# ATSAM4E16EA_AU_Main_Controller.net
KiCad netlist of a schematic drawn in Altium Designer
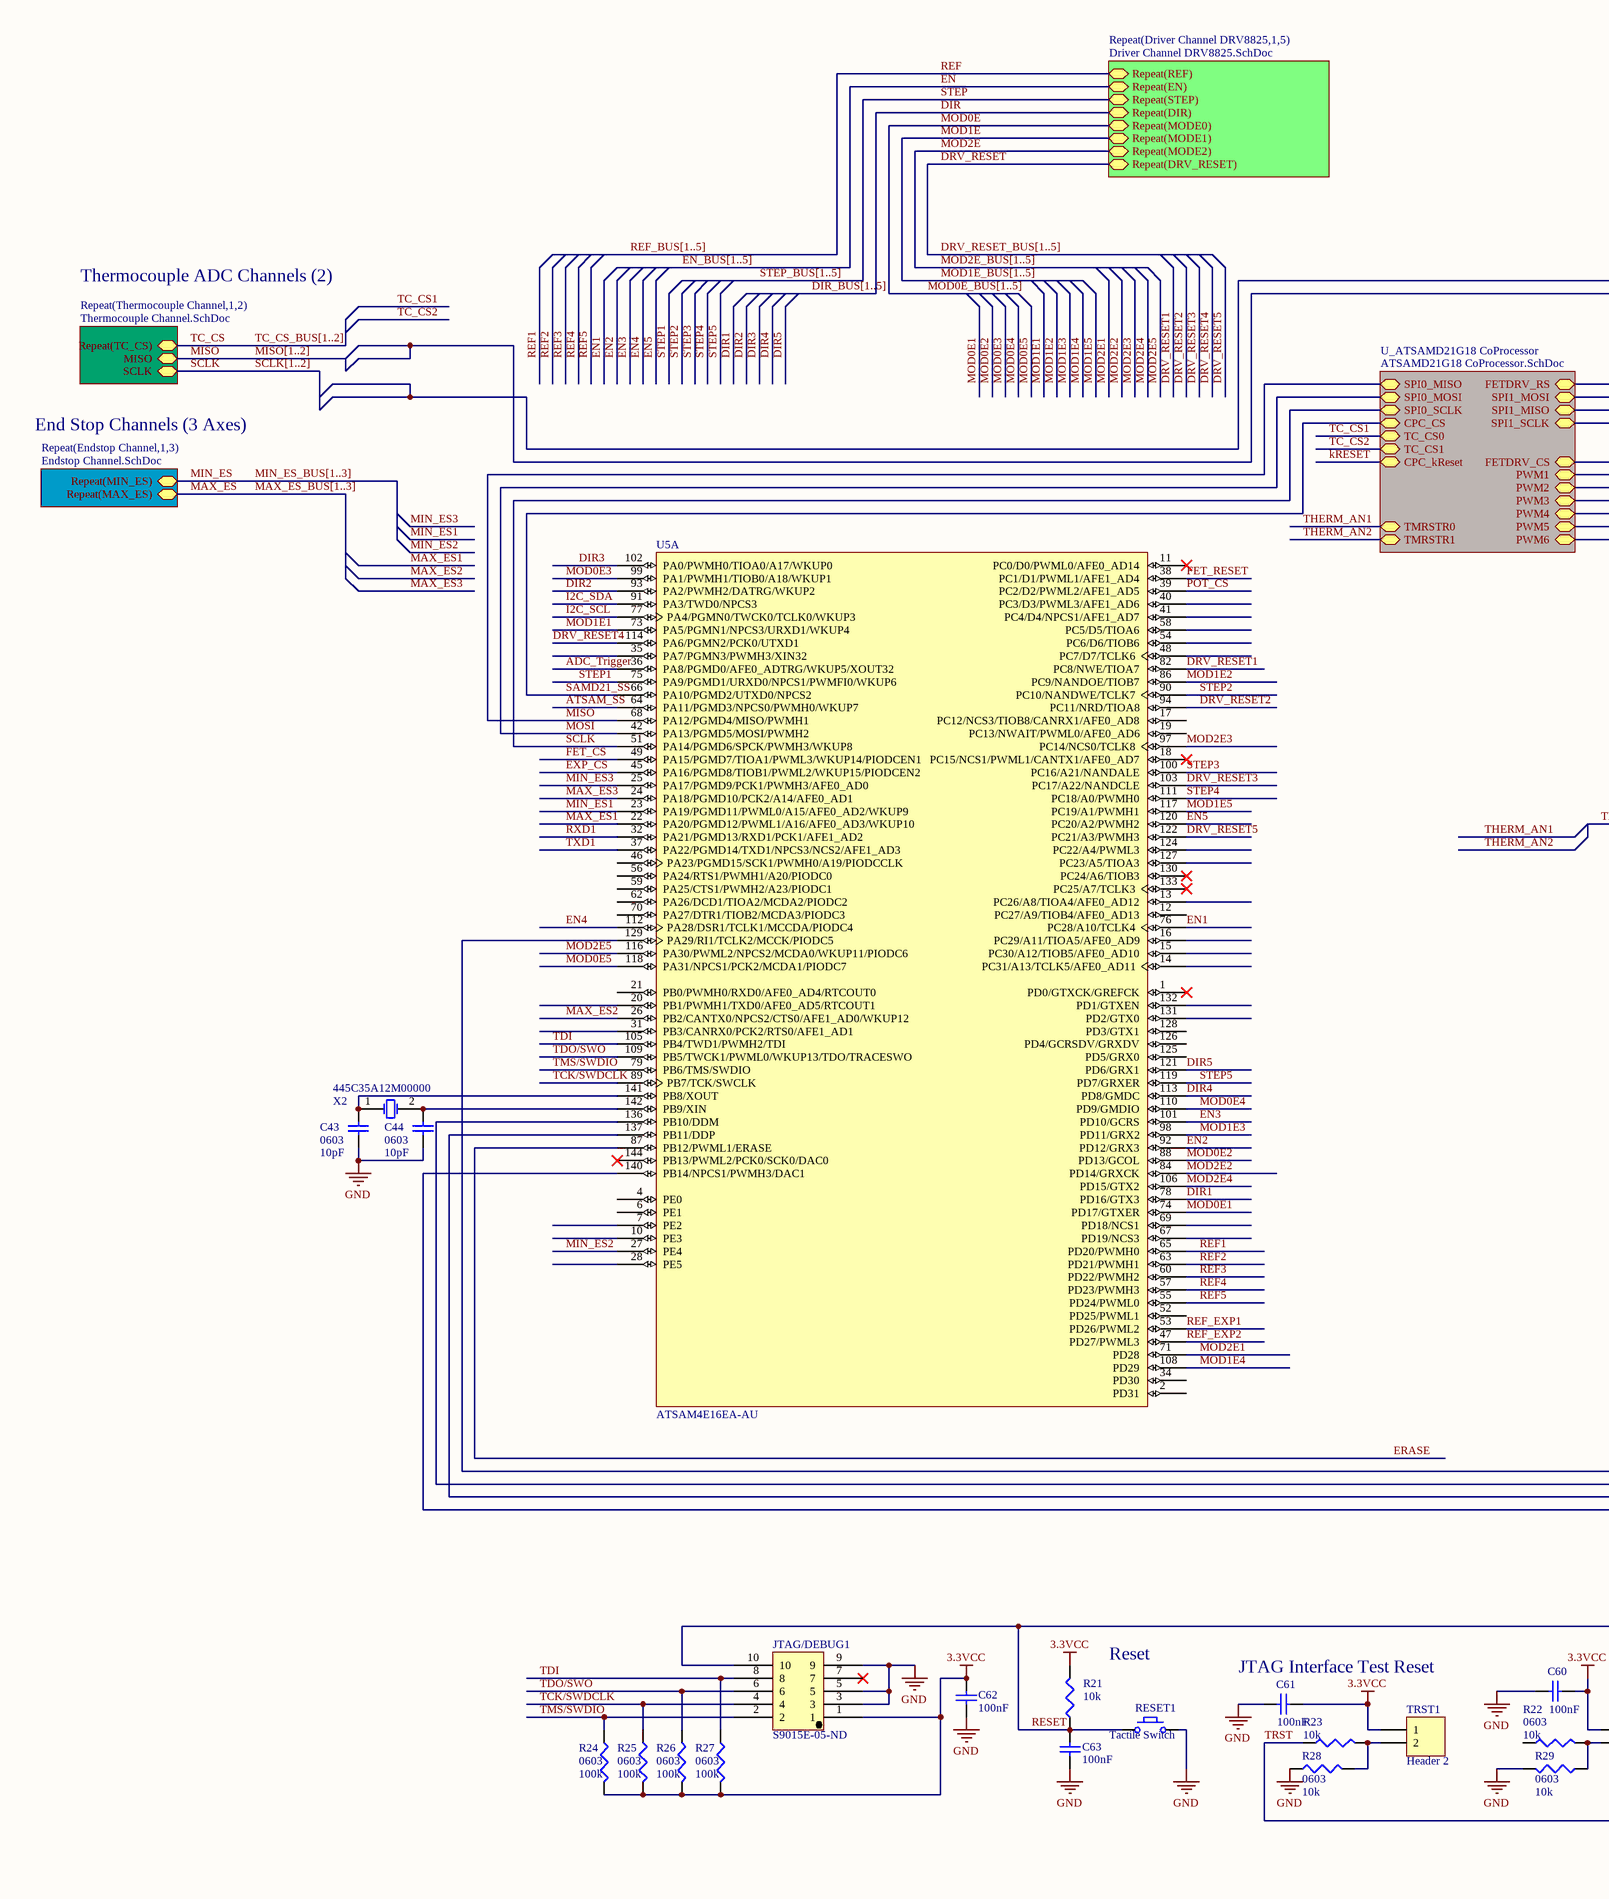
[diagram p0: ATSAM4E16EA_AU Main Controller.SchDoc, left]
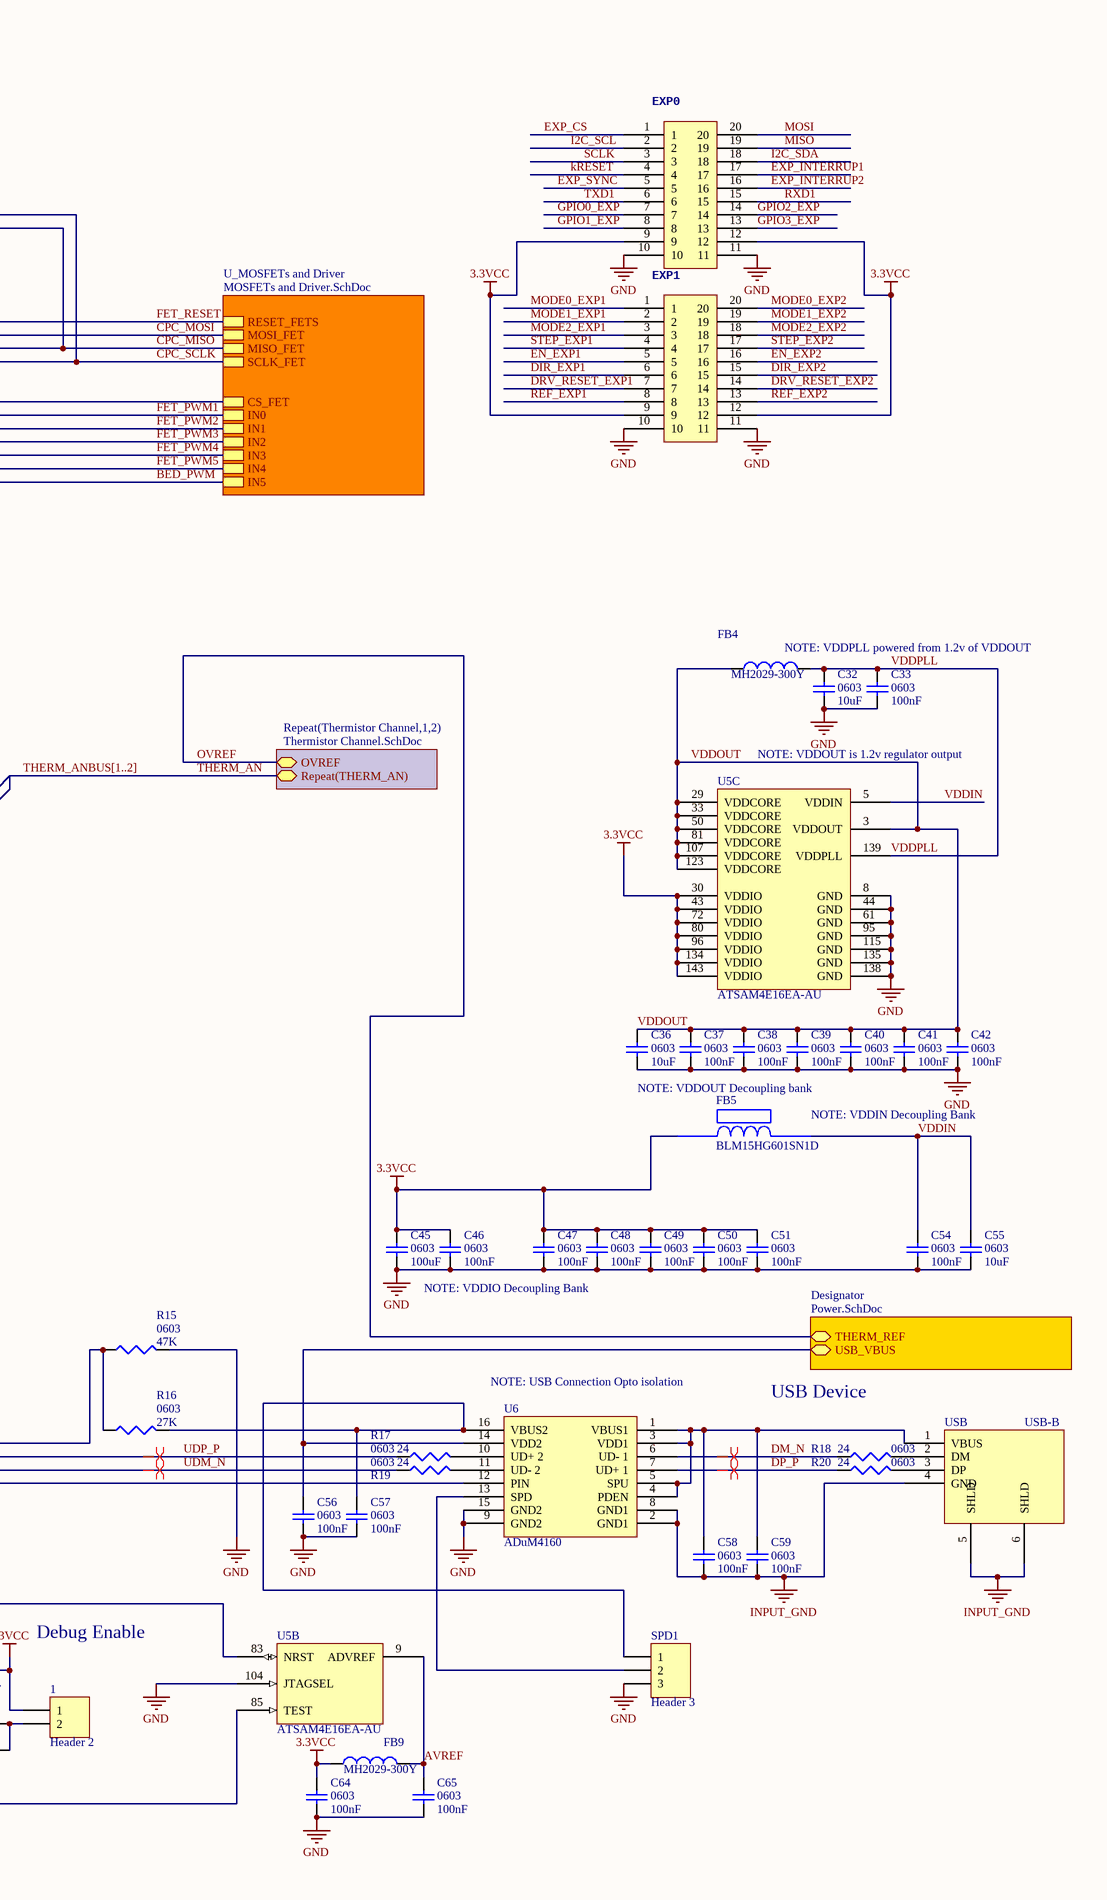
[diagram p1: ATSAM4E16EA_AU Main Controller.SchDoc, right]

(export (version "E")
  (design (tool "Eeschema 10.0.6"))
  (components
    (comp (ref "1")
      (value "Header 2")
      (footprint "HDR1X2")
      (description "Header, 2-Pin")
      (fields (field (name "PUBLISHER") "Altium Limited"))
      (libsource (lib "Miscellaneous Connectors") (part "Header 2"))
    )
    (comp (ref "C32")
      (value "0603")
      (footprint "1608[0603]")
      (description "Capacitor (Semiconductor SIM Model)")
      (fields (field (name "ALTIUM_VALUE") "10uF") (field (name "PUBLISHER") "Altium Limited"))
      (libsource (lib "Miscellaneous Devices") (part "Cap Semi"))
    )
    (comp (ref "C33")
      (value "0603")
      (footprint "1608[0603]")
      (description "Capacitor (Semiconductor SIM Model)")
      (fields (field (name "ALTIUM_VALUE") "100nF") (field (name "PUBLISHER") "Altium Limited"))
      (libsource (lib "Miscellaneous Devices") (part "Cap Semi"))
    )
    (comp (ref "C36")
      (value "0603")
      (footprint "1608[0603]")
      (description "Capacitor (Semiconductor SIM Model)")
      (fields (field (name "ALTIUM_VALUE") "10uF") (field (name "PUBLISHER") "Altium Limited"))
      (libsource (lib "Miscellaneous Devices") (part "Cap Semi"))
    )
    (comp (ref "C37")
      (value "0603")
      (footprint "1608[0603]")
      (description "Capacitor (Semiconductor SIM Model)")
      (fields (field (name "ALTIUM_VALUE") "100nF") (field (name "PUBLISHER") "Altium Limited"))
      (libsource (lib "Miscellaneous Devices") (part "Cap Semi"))
    )
    (comp (ref "C38")
      (value "0603")
      (footprint "1608[0603]")
      (description "Capacitor (Semiconductor SIM Model)")
      (fields (field (name "ALTIUM_VALUE") "100nF") (field (name "PUBLISHER") "Altium Limited"))
      (libsource (lib "Miscellaneous Devices") (part "Cap Semi"))
    )
    (comp (ref "C39")
      (value "0603")
      (footprint "1608[0603]")
      (description "Capacitor (Semiconductor SIM Model)")
      (fields (field (name "ALTIUM_VALUE") "100nF") (field (name "PUBLISHER") "Altium Limited"))
      (libsource (lib "Miscellaneous Devices") (part "Cap Semi"))
    )
    (comp (ref "C40")
      (value "0603")
      (footprint "1608[0603]")
      (description "Capacitor (Semiconductor SIM Model)")
      (fields (field (name "ALTIUM_VALUE") "100nF") (field (name "PUBLISHER") "Altium Limited"))
      (libsource (lib "Miscellaneous Devices") (part "Cap Semi"))
    )
    (comp (ref "C41")
      (value "0603")
      (footprint "1608[0603]")
      (description "Capacitor (Semiconductor SIM Model)")
      (fields (field (name "ALTIUM_VALUE") "100nF") (field (name "PUBLISHER") "Altium Limited"))
      (libsource (lib "Miscellaneous Devices") (part "Cap Semi"))
    )
    (comp (ref "C42")
      (value "0603")
      (footprint "1608[0603]")
      (description "Capacitor (Semiconductor SIM Model)")
      (fields (field (name "ALTIUM_VALUE") "100nF") (field (name "PUBLISHER") "Altium Limited"))
      (libsource (lib "Miscellaneous Devices") (part "Cap Semi"))
    )
    (comp (ref "C43")
      (value "0603")
      (footprint "1608[0603]")
      (description "Capacitor (Semiconductor SIM Model)")
      (fields (field (name "ALTIUM_VALUE") "10pF") (field (name "PUBLISHER") "Altium Limited"))
      (libsource (lib "Miscellaneous Devices") (part "Cap Semi"))
    )
    (comp (ref "C44")
      (value "0603")
      (footprint "1608[0603]")
      (description "Capacitor (Semiconductor SIM Model)")
      (fields (field (name "ALTIUM_VALUE") "10pF") (field (name "PUBLISHER") "Altium Limited"))
      (libsource (lib "Miscellaneous Devices") (part "Cap Semi"))
    )
    (comp (ref "C45")
      (value "0603")
      (footprint "1608[0603]")
      (description "Capacitor (Semiconductor SIM Model)")
      (fields (field (name "ALTIUM_VALUE") "100uF") (field (name "PUBLISHER") "Altium Limited"))
      (libsource (lib "Miscellaneous Devices") (part "Cap Semi"))
    )
    (comp (ref "C46")
      (value "0603")
      (footprint "1608[0603]")
      (description "Capacitor (Semiconductor SIM Model)")
      (fields (field (name "ALTIUM_VALUE") "100nF") (field (name "PUBLISHER") "Altium Limited"))
      (libsource (lib "Miscellaneous Devices") (part "Cap Semi"))
    )
    (comp (ref "C47")
      (value "0603")
      (footprint "1608[0603]")
      (description "Capacitor (Semiconductor SIM Model)")
      (fields (field (name "ALTIUM_VALUE") "100nF") (field (name "PUBLISHER") "Altium Limited"))
      (libsource (lib "Miscellaneous Devices") (part "Cap Semi"))
    )
    (comp (ref "C48")
      (value "0603")
      (footprint "1608[0603]")
      (description "Capacitor (Semiconductor SIM Model)")
      (fields (field (name "ALTIUM_VALUE") "100nF") (field (name "PUBLISHER") "Altium Limited"))
      (libsource (lib "Miscellaneous Devices") (part "Cap Semi"))
    )
    (comp (ref "C49")
      (value "0603")
      (footprint "1608[0603]")
      (description "Capacitor (Semiconductor SIM Model)")
      (fields (field (name "ALTIUM_VALUE") "100nF") (field (name "PUBLISHER") "Altium Limited"))
      (libsource (lib "Miscellaneous Devices") (part "Cap Semi"))
    )
    (comp (ref "C50")
      (value "0603")
      (footprint "1608[0603]")
      (description "Capacitor (Semiconductor SIM Model)")
      (fields (field (name "ALTIUM_VALUE") "100nF") (field (name "PUBLISHER") "Altium Limited"))
      (libsource (lib "Miscellaneous Devices") (part "Cap Semi"))
    )
    (comp (ref "C51")
      (value "0603")
      (footprint "1608[0603]")
      (description "Capacitor (Semiconductor SIM Model)")
      (fields (field (name "ALTIUM_VALUE") "100nF") (field (name "PUBLISHER") "Altium Limited"))
      (libsource (lib "Miscellaneous Devices") (part "Cap Semi"))
    )
    (comp (ref "C54")
      (value "0603")
      (footprint "1608[0603]")
      (description "Capacitor (Semiconductor SIM Model)")
      (fields (field (name "ALTIUM_VALUE") "100nF") (field (name "PUBLISHER") "Altium Limited"))
      (libsource (lib "Miscellaneous Devices") (part "Cap Semi"))
    )
    (comp (ref "C55")
      (value "0603")
      (footprint "1608[0603]")
      (description "Capacitor (Semiconductor SIM Model)")
      (fields (field (name "ALTIUM_VALUE") "10uF") (field (name "PUBLISHER") "Altium Limited"))
      (libsource (lib "Miscellaneous Devices") (part "Cap Semi"))
    )
    (comp (ref "C56")
      (value "0603")
      (footprint "1608[0603]")
      (description "Capacitor (Semiconductor SIM Model)")
      (fields (field (name "ALTIUM_VALUE") "100nF") (field (name "PUBLISHER") "Altium Limited"))
      (libsource (lib "Miscellaneous Devices") (part "Cap Semi"))
    )
    (comp (ref "C57")
      (value "0603")
      (footprint "1608[0603]")
      (description "Capacitor (Semiconductor SIM Model)")
      (fields (field (name "ALTIUM_VALUE") "100nF") (field (name "PUBLISHER") "Altium Limited"))
      (libsource (lib "Miscellaneous Devices") (part "Cap Semi"))
    )
    (comp (ref "C58")
      (value "0603")
      (footprint "1608[0603]")
      (description "Capacitor (Semiconductor SIM Model)")
      (fields (field (name "ALTIUM_VALUE") "100nF") (field (name "PUBLISHER") "Altium Limited"))
      (libsource (lib "Miscellaneous Devices") (part "Cap Semi"))
    )
    (comp (ref "C59")
      (value "0603")
      (footprint "1608[0603]")
      (description "Capacitor (Semiconductor SIM Model)")
      (fields (field (name "ALTIUM_VALUE") "100nF") (field (name "PUBLISHER") "Altium Limited"))
      (libsource (lib "Miscellaneous Devices") (part "Cap Semi"))
    )
    (comp (ref "C60")
      (value "100nF")
      (footprint "1608[0603]")
      (description "Capacitor (Semiconductor SIM Model)")
      (fields (field (name "Comment") "Cap Semi") (field (name "PUBLISHER") "Altium Limited"))
      (libsource (lib "Miscellaneous Devices") (part "Cap Semi"))
    )
    (comp (ref "C61")
      (value "100nF")
      (footprint "1608[0603]")
      (description "Capacitor (Semiconductor SIM Model)")
      (fields (field (name "Comment") "Cap Semi") (field (name "PUBLISHER") "Altium Limited"))
      (libsource (lib "Miscellaneous Devices") (part "Cap Semi"))
    )
    (comp (ref "C62")
      (value "100nF")
      (footprint "1608[0603]")
      (description "Capacitor (Semiconductor SIM Model)")
      (fields (field (name "Comment") "Cap Semi") (field (name "PUBLISHER") "Altium Limited"))
      (libsource (lib "Miscellaneous Devices") (part "Cap Semi"))
    )
    (comp (ref "C63")
      (value "100nF")
      (footprint "1608[0603]")
      (description "Capacitor (Semiconductor SIM Model)")
      (fields (field (name "Comment") "Cap Semi") (field (name "PUBLISHER") "Altium Limited"))
      (libsource (lib "Miscellaneous Devices") (part "Cap Semi"))
    )
    (comp (ref "C64")
      (value "0603")
      (footprint "1608[0603]")
      (description "Capacitor (Semiconductor SIM Model)")
      (fields (field (name "ALTIUM_VALUE") "100nF") (field (name "PUBLISHER") "Altium Limited"))
      (libsource (lib "Miscellaneous Devices") (part "Cap Semi"))
    )
    (comp (ref "C65")
      (value "0603")
      (footprint "1608[0603]")
      (description "Capacitor (Semiconductor SIM Model)")
      (fields (field (name "ALTIUM_VALUE") "100nF") (field (name "PUBLISHER") "Altium Limited"))
      (libsource (lib "Miscellaneous Devices") (part "Cap Semi"))
    )
    (comp (ref "EXP0")
      (value "10X2-0.1X0.05")
      (footprint "10X2-0.05X0.1")
      (fields (field (name "PUBLISHER") "UltiMachine"))
      (libsource (lib "ZMBo Schematic Library") (part "10X2-0.1X0.05"))
    )
    (comp (ref "EXP1")
      (value "10X2-0.1X0.05")
      (footprint "10X2-0.05X0.1")
      (fields (field (name "PUBLISHER") "UltiMachine"))
      (libsource (lib "ZMBo Schematic Library") (part "10X2-0.1X0.05"))
    )
    (comp (ref "FB4")
      (value "MH2029-300Y")
      (footprint "SM 0805 - gap trimmed")
      (description "Inductor")
      (fields (field (name "PUBLISHER") "Altium Limited"))
      (libsource (lib "Miscellaneous Devices") (part "Inductor"))
    )
    (comp (ref "FB5")
      (value "BLM15HG601SN1D")
      (footprint "BLM18PG121SN1D")
      (libsource (lib "AHD Part Library") (part "BLM15HG601SN1D"))
    )
    (comp (ref "FB9")
      (value "MH2029-300Y")
      (footprint "SM 0805 - gap trimmed")
      (description "Inductor")
      (fields (field (name "PUBLISHER") "Altium Limited"))
      (libsource (lib "Miscellaneous Devices") (part "Inductor"))
    )
    (comp (ref "JTAG/DEBUG1")
      (value "S9015E-05-ND")
      (footprint "S9015E-05-ND")
      (libsource (lib "AHD Part Library") (part "S9015E-05-ND"))
    )
    (comp (ref "R15")
      (value "0603")
      (footprint "J1-0603")
      (description "Resistor")
      (fields (field (name "ALTIUM_VALUE") "47K") (field (name "PUBLISHER") "Altium Limited"))
      (libsource (lib "Miscellaneous Devices") (part "Res3"))
    )
    (comp (ref "R16")
      (value "0603")
      (footprint "J1-0603")
      (description "Resistor")
      (fields (field (name "ALTIUM_VALUE") "27K") (field (name "PUBLISHER") "Altium Limited"))
      (libsource (lib "Miscellaneous Devices") (part "Res3"))
    )
    (comp (ref "R17")
      (value "0603")
      (footprint "J1-0603")
      (description "Resistor")
      (fields (field (name "ALTIUM_VALUE") "24") (field (name "PUBLISHER") "Altium Limited"))
      (libsource (lib "Miscellaneous Devices") (part "Res3"))
    )
    (comp (ref "R18")
      (value "0603")
      (footprint "J1-0603")
      (description "Resistor")
      (fields (field (name "ALTIUM_VALUE") "24") (field (name "PUBLISHER") "Altium Limited"))
      (libsource (lib "Miscellaneous Devices") (part "Res3"))
    )
    (comp (ref "R19")
      (value "0603")
      (footprint "J1-0603")
      (description "Resistor")
      (fields (field (name "ALTIUM_VALUE") "24") (field (name "PUBLISHER") "Altium Limited"))
      (libsource (lib "Miscellaneous Devices") (part "Res3"))
    )
    (comp (ref "R20")
      (value "0603")
      (footprint "J1-0603")
      (description "Resistor")
      (fields (field (name "ALTIUM_VALUE") "24") (field (name "PUBLISHER") "Altium Limited"))
      (libsource (lib "Miscellaneous Devices") (part "Res3"))
    )
    (comp (ref "R21")
      (value "10k")
      (footprint "J1-0603")
      (description "Resistor")
      (fields (field (name "Comment") "Res3") (field (name "PUBLISHER") "Altium Limited"))
      (libsource (lib "Miscellaneous Devices") (part "Res3"))
    )
    (comp (ref "R22")
      (value "0603")
      (footprint "J1-0603")
      (description "Resistor")
      (fields (field (name "ALTIUM_VALUE") "10k") (field (name "PUBLISHER") "Altium Limited"))
      (libsource (lib "Miscellaneous Devices") (part "Res3"))
    )
    (comp (ref "R23")
      (value "10k")
      (footprint "J1-0603")
      (description "Resistor")
      (fields (field (name "Comment") "Res3") (field (name "PUBLISHER") "Altium Limited"))
      (libsource (lib "Miscellaneous Devices") (part "Res3"))
    )
    (comp (ref "R24")
      (value "0603")
      (footprint "J1-0603")
      (description "Resistor")
      (fields (field (name "ALTIUM_VALUE") "100k") (field (name "PUBLISHER") "Altium Limited"))
      (libsource (lib "Miscellaneous Devices") (part "Res3"))
    )
    (comp (ref "R25")
      (value "0603")
      (footprint "J1-0603")
      (description "Resistor")
      (fields (field (name "ALTIUM_VALUE") "100k") (field (name "PUBLISHER") "Altium Limited"))
      (libsource (lib "Miscellaneous Devices") (part "Res3"))
    )
    (comp (ref "R26")
      (value "0603")
      (footprint "J1-0603")
      (description "Resistor")
      (fields (field (name "ALTIUM_VALUE") "100k") (field (name "PUBLISHER") "Altium Limited"))
      (libsource (lib "Miscellaneous Devices") (part "Res3"))
    )
    (comp (ref "R27")
      (value "0603")
      (footprint "J1-0603")
      (description "Resistor")
      (fields (field (name "ALTIUM_VALUE") "100k") (field (name "PUBLISHER") "Altium Limited"))
      (libsource (lib "Miscellaneous Devices") (part "Res3"))
    )
    (comp (ref "R28")
      (value "0603")
      (footprint "J1-0603")
      (description "Resistor")
      (fields (field (name "ALTIUM_VALUE") "10k") (field (name "PUBLISHER") "Altium Limited"))
      (libsource (lib "Miscellaneous Devices") (part "Res3"))
    )
    (comp (ref "R29")
      (value "0603")
      (footprint "J1-0603")
      (description "Resistor")
      (fields (field (name "ALTIUM_VALUE") "10k") (field (name "PUBLISHER") "Altium Limited"))
      (libsource (lib "Miscellaneous Devices") (part "Res3"))
    )
    (comp (ref "RESET1")
      (value "Tactile Switch")
      (footprint "TL3301")
      (libsource (lib "Adams Altium Library") (part "Tactile Switch"))
    )
    (comp (ref "SPD1")
      (value "Header 3")
      (footprint "HDR1X3")
      (description "Header, 3-Pin")
      (fields (field (name "PUBLISHER") "Altium Limited"))
      (libsource (lib "Miscellaneous Connectors") (part "Header 3"))
    )
    (comp (ref "TRST1")
      (value "Header 2")
      (footprint "HDR1X2")
      (description "Header, 2-Pin")
      (fields (field (name "PUBLISHER") "Altium Limited"))
      (libsource (lib "Miscellaneous Connectors") (part "Header 2"))
    )
    (comp (ref "U5")
      (value "ATSAM4E16EA-AU")
      (footprint "LQFP144_N")
      (libsource (lib "ZMBo Schematic Library") (part "ATML-ATSAM4EXEA-LQFP-144"))
    )
    (comp (ref "U6")
      (value "ADuM4160")
      (footprint "ADuM4160")
      (description "USB Opto Isolator")
      (libsource (lib "ZMBo Schematic Library") (part "ADuM4160"))
    )
    (comp (ref "USB")
      (value "USB-B")
      (footprint "PN61729")
      (libsource (lib "ZMBo Schematic Library") (part "USB-B"))
    )
    (comp (ref "X2")
      (value "445C35A12M00000")
      (footprint "445C35A12M00000")
      (description "Crystal Oscillator")
      (fields (field (name "PUBLISHER") "Altium Limited"))
      (libsource (lib "Miscellaneous Devices") (part "XTAL"))
    )
  )
  (nets
    (net (code "55") (name "/ADC_Trigger") (class "Default")
      (node (ref "U5") (pin "36") (pinfunction "PA8/PGMD0/AFE0_ADTRG/WKUP5/XOUT32_36") (pintype "bidirectional"))
    )
    (net (code "56") (name "/ATSAM_SS") (class "Default")
      (node (ref "U5") (pin "64") (pinfunction "PA11/PGMD3/NPCS0/PWMH0/WKUP7_64") (pintype "bidirectional"))
    )
    (net (code "57") (name "/AVREF") (class "Default")
      (node (ref "C65") (pin "2") (pinfunction "2_2") (pintype "passive"))
      (node (ref "FB9") (pin "2") (pinfunction "2_2") (pintype "passive"))
      (node (ref "U5") (pin "9") (pinfunction "ADVREF_9") (pintype "passive"))
    )
    (net (code "64") (name "/DIR1") (class "Default")
      (node (ref "U5") (pin "78") (pinfunction "PD16/GTX3_78") (pintype "bidirectional"))
    )
    (net (code "65") (name "/DIR2") (class "Default")
      (node (ref "U5") (pin "93") (pinfunction "PA2/PWMH2/DATRG/WKUP2_93") (pintype "bidirectional"))
    )
    (net (code "66") (name "/DIR3") (class "Default")
      (node (ref "U5") (pin "102") (pinfunction "PA0/PWMH0/TIOA0/A17/WKUP0_102") (pintype "bidirectional"))
    )
    (net (code "67") (name "/DIR4") (class "Default")
      (node (ref "U5") (pin "113") (pinfunction "PD8/GMDC_113") (pintype "bidirectional"))
    )
    (net (code "68") (name "/DIR5") (class "Default")
      (node (ref "U5") (pin "121") (pinfunction "PD6/GRX1_121") (pintype "bidirectional"))
    )
    (net (code "70") (name "/DIR_EXP1") (class "Default")
      (node (ref "EXP1") (pin "6") (pinfunction "6_6") (pintype "passive"))
    )
    (net (code "71") (name "/DIR_EXP2") (class "Default")
      (node (ref "EXP1") (pin "15") (pinfunction "15_15") (pintype "passive"))
    )
    (net (code "72") (name "/DM_N") (class "Default")
      (node (ref "R18") (pin "1") (pinfunction "1_1") (pintype "passive"))
      (node (ref "U6") (pin "6") (pinfunction "UD-_1_6") (pintype "passive"))
    )
    (net (code "73") (name "/DP_P") (class "Default")
      (node (ref "R20") (pin "1") (pinfunction "1_1") (pintype "passive"))
      (node (ref "U6") (pin "7") (pinfunction "UD+_1_7") (pintype "passive"))
    )
    (net (code "75") (name "/DRV_RESET1") (class "Default")
      (node (ref "U5") (pin "82") (pinfunction "PC8/NWE/TIOA7_82") (pintype "bidirectional"))
    )
    (net (code "76") (name "/DRV_RESET2") (class "Default")
      (node (ref "U5") (pin "94") (pinfunction "PC11/NRD/TIOA8_94") (pintype "bidirectional"))
    )
    (net (code "77") (name "/DRV_RESET3") (class "Default")
      (node (ref "U5") (pin "103") (pinfunction "PC17/A22/NANDCLE_103") (pintype "bidirectional"))
    )
    (net (code "78") (name "/DRV_RESET4") (class "Default")
      (node (ref "U5") (pin "114") (pinfunction "PA6/PGMN2/PCK0/UTXD1_114") (pintype "bidirectional"))
    )
    (net (code "79") (name "/DRV_RESET5") (class "Default")
      (node (ref "U5") (pin "122") (pinfunction "PC21/A3/PWMH3_122") (pintype "bidirectional"))
    )
    (net (code "81") (name "/DRV_RESET_EXP1") (class "Default")
      (node (ref "EXP1") (pin "7") (pinfunction "7_7") (pintype "passive"))
    )
    (net (code "82") (name "/DRV_RESET_EXP2") (class "Default")
      (node (ref "EXP1") (pin "14") (pinfunction "14_14") (pintype "passive"))
    )
    (net (code "84") (name "/EN1") (class "Default")
      (node (ref "U5") (pin "76") (pinfunction "PC28/A10/TCLK4_76") (pintype "bidirectional"))
    )
    (net (code "85") (name "/EN2") (class "Default")
      (node (ref "U5") (pin "92") (pinfunction "PD12/GRX3_92") (pintype "bidirectional"))
    )
    (net (code "86") (name "/EN3") (class "Default")
      (node (ref "U5") (pin "101") (pinfunction "PD10/GCRS_101") (pintype "bidirectional"))
    )
    (net (code "87") (name "/EN4") (class "Default")
      (node (ref "U5") (pin "112") (pinfunction "PA28/DSR1/TCLK1/MCCDA/PIODC4_112") (pintype "bidirectional"))
    )
    (net (code "88") (name "/EN5") (class "Default")
      (node (ref "U5") (pin "120") (pinfunction "PC20/A2/PWMH2_120") (pintype "bidirectional"))
    )
    (net (code "90") (name "/EN_EXP1") (class "Default")
      (node (ref "EXP1") (pin "5") (pinfunction "5_5") (pintype "passive"))
    )
    (net (code "91") (name "/EN_EXP2") (class "Default")
      (node (ref "EXP1") (pin "16") (pinfunction "16_16") (pintype "passive"))
    )
    (net (code "92") (name "/ERASE") (class "Default")
      (node (ref "U5") (pin "87") (pinfunction "PB12/PWML1/ERASE_87") (pintype "bidirectional"))
    )
    (net (code "93") (name "/EXP_CS") (class "Default")
      (node (ref "EXP0") (pin "1") (pinfunction "1_1") (pintype "passive"))
      (node (ref "U5") (pin "45") (pinfunction "PA16/PGMD8/TIOB1/PWML2/WKUP15/PIODCEN2_45") (pintype "bidirectional"))
    )
    (net (code "94") (name "/EXP_INTERRUP1") (class "Default")
      (node (ref "EXP0") (pin "17") (pinfunction "17_17") (pintype "passive"))
    )
    (net (code "95") (name "/EXP_INTERRUP2") (class "Default")
      (node (ref "EXP0") (pin "16") (pinfunction "16_16") (pintype "passive"))
    )
    (net (code "96") (name "/EXP_SYNC") (class "Default")
      (node (ref "EXP0") (pin "5") (pinfunction "5_5") (pintype "passive"))
    )
    (net (code "97") (name "/FET_CS") (class "Default")
      (node (ref "U5") (pin "49") (pinfunction "PA15/PGMD7/TIOA1/PWML3/WKUP14/PIODCEN1_49") (pintype "bidirectional"))
    )
    (net (code "103") (name "/FET_RESET") (class "Default")
      (node (ref "U5") (pin "38") (pinfunction "PC1/D1/PWML1/AFE1_AD4_38") (pintype "bidirectional"))
    )
    (net (code "104") (name "/GPIO0_EXP") (class "Default")
      (node (ref "EXP0") (pin "7") (pinfunction "7_7") (pintype "passive"))
    )
    (net (code "105") (name "/GPIO1_EXP") (class "Default")
      (node (ref "EXP0") (pin "8") (pinfunction "8_8") (pintype "passive"))
    )
    (net (code "106") (name "/GPIO2_EXP") (class "Default")
      (node (ref "EXP0") (pin "14") (pinfunction "14_14") (pintype "passive"))
    )
    (net (code "107") (name "/GPIO3_EXP") (class "Default")
      (node (ref "EXP0") (pin "13") (pinfunction "13_13") (pintype "passive"))
    )
    (net (code "108") (name "/I2C_SCL") (class "Default")
      (node (ref "EXP0") (pin "2") (pinfunction "2_2") (pintype "passive"))
      (node (ref "U5") (pin "77") (pinfunction "PA4/PGMN0/TWCK0/TCLK0/WKUP3_77") (pintype "bidirectional"))
    )
    (net (code "109") (name "/I2C_SDA") (class "Default")
      (node (ref "EXP0") (pin "18") (pinfunction "18_18") (pintype "passive"))
      (node (ref "U5") (pin "91") (pinfunction "PA3/TWD0/NPCS3_91") (pintype "bidirectional"))
    )
    (net (code "111") (name "/MAX_ES1") (class "Default")
      (node (ref "U5") (pin "22") (pinfunction "PA20/PGMD12/PWML1/A16/AFE0_AD3/WKUP10_22") (pintype "bidirectional"))
    )
    (net (code "112") (name "/MAX_ES2") (class "Default")
      (node (ref "U5") (pin "26") (pinfunction "PB2/CANTX0/NPCS2/CTS0/AFE1_AD0/WKUP12_26") (pintype "bidirectional"))
    )
    (net (code "113") (name "/MAX_ES3") (class "Default")
      (node (ref "U5") (pin "24") (pinfunction "PA18/PGMD10/PCK2/A14/AFE0_AD1_24") (pintype "bidirectional"))
    )
    (net (code "116") (name "/MIN_ES1") (class "Default")
      (node (ref "U5") (pin "23") (pinfunction "PA19/PGMD11/PWML0/A15/AFE0_AD2/WKUP9_23") (pintype "bidirectional"))
    )
    (net (code "117") (name "/MIN_ES2") (class "Default")
      (node (ref "U5") (pin "27") (pinfunction "PE4_27") (pintype "bidirectional"))
    )
    (net (code "118") (name "/MIN_ES3") (class "Default")
      (node (ref "U5") (pin "25") (pinfunction "PA17/PGMD9/PCK1/PWMH3/AFE0_AD0_25") (pintype "bidirectional"))
    )
    (net (code "120") (name "/MISO") (class "Default")
      (node (ref "EXP0") (pin "19") (pinfunction "19_19") (pintype "passive"))
      (node (ref "U5") (pin "68") (pinfunction "PA12/PGMD4/MISO/PWMH1_68") (pintype "bidirectional"))
    )
    (net (code "123") (name "/MOD0E1") (class "Default")
      (node (ref "U5") (pin "74") (pinfunction "PD17/GTXER_74") (pintype "bidirectional"))
    )
    (net (code "124") (name "/MOD0E2") (class "Default")
      (node (ref "U5") (pin "88") (pinfunction "PD13/GCOL_88") (pintype "bidirectional"))
    )
    (net (code "125") (name "/MOD0E3") (class "Default")
      (node (ref "U5") (pin "99") (pinfunction "PA1/PWMH1/TIOB0/A18/WKUP1_99") (pintype "bidirectional"))
    )
    (net (code "126") (name "/MOD0E4") (class "Default")
      (node (ref "U5") (pin "110") (pinfunction "PD9/GMDIO_110") (pintype "bidirectional"))
    )
    (net (code "127") (name "/MOD0E5") (class "Default")
      (node (ref "U5") (pin "118") (pinfunction "PA31/NPCS1/PCK2/MCDA1/PIODC7_118") (pintype "bidirectional"))
    )
    (net (code "130") (name "/MOD1E1") (class "Default")
      (node (ref "U5") (pin "73") (pinfunction "PA5/PGMN1/NPCS3/URXD1/WKUP4_73") (pintype "bidirectional"))
    )
    (net (code "131") (name "/MOD1E2") (class "Default")
      (node (ref "U5") (pin "86") (pinfunction "PC9/NANDOE/TIOB7_86") (pintype "bidirectional"))
    )
    (net (code "132") (name "/MOD1E3") (class "Default")
      (node (ref "U5") (pin "98") (pinfunction "PD11/GRX2_98") (pintype "bidirectional"))
    )
    (net (code "133") (name "/MOD1E4") (class "Default")
      (node (ref "U5") (pin "108") (pinfunction "PD29_108") (pintype "bidirectional"))
    )
    (net (code "134") (name "/MOD1E5") (class "Default")
      (node (ref "U5") (pin "117") (pinfunction "PC19/A1/PWMH1_117") (pintype "bidirectional"))
    )
    (net (code "137") (name "/MOD2E1") (class "Default")
      (node (ref "U5") (pin "71") (pinfunction "PD28_71") (pintype "bidirectional"))
    )
    (net (code "138") (name "/MOD2E2") (class "Default")
      (node (ref "U5") (pin "84") (pinfunction "PD14/GRXCK_84") (pintype "bidirectional"))
    )
    (net (code "139") (name "/MOD2E3") (class "Default")
      (node (ref "U5") (pin "97") (pinfunction "PC14/NCS0/TCLK8_97") (pintype "bidirectional"))
    )
    (net (code "140") (name "/MOD2E4") (class "Default")
      (node (ref "U5") (pin "106") (pinfunction "PD15/GTX2_106") (pintype "bidirectional"))
    )
    (net (code "141") (name "/MOD2E5") (class "Default")
      (node (ref "U5") (pin "116") (pinfunction "PA30/PWML2/NPCS2/MCDA0/WKUP11/PIODC6_116") (pintype "bidirectional"))
    )
    (net (code "143") (name "/MODE0_EXP1") (class "Default")
      (node (ref "EXP1") (pin "1") (pinfunction "1_1") (pintype "passive"))
    )
    (net (code "144") (name "/MODE0_EXP2") (class "Default")
      (node (ref "EXP1") (pin "20") (pinfunction "20_20") (pintype "passive"))
    )
    (net (code "145") (name "/MODE1_EXP1") (class "Default")
      (node (ref "EXP1") (pin "2") (pinfunction "2_2") (pintype "passive"))
    )
    (net (code "146") (name "/MODE1_EXP2") (class "Default")
      (node (ref "EXP1") (pin "19") (pinfunction "19_19") (pintype "passive"))
    )
    (net (code "147") (name "/MODE2_EXP1") (class "Default")
      (node (ref "EXP1") (pin "3") (pinfunction "3_3") (pintype "passive"))
    )
    (net (code "148") (name "/MODE2_EXP2") (class "Default")
      (node (ref "EXP1") (pin "18") (pinfunction "18_18") (pintype "passive"))
    )
    (net (code "149") (name "/MOSI") (class "Default")
      (node (ref "EXP0") (pin "20") (pinfunction "20_20") (pintype "passive"))
      (node (ref "U5") (pin "42") (pinfunction "PA13/PGMD5/MOSI/PWMH2_42") (pintype "bidirectional"))
    )
    (net (code "151") (name "/POT_CS") (class "Default")
      (node (ref "U5") (pin "39") (pinfunction "PC2/D2/PWML2/AFE1_AD5_39") (pintype "bidirectional"))
    )
    (net (code "153") (name "/REF1") (class "Default")
      (node (ref "U5") (pin "65") (pinfunction "PD20/PWMH0_65") (pintype "bidirectional"))
    )
    (net (code "154") (name "/REF2") (class "Default")
      (node (ref "U5") (pin "63") (pinfunction "PD21/PWMH1_63") (pintype "bidirectional"))
    )
    (net (code "155") (name "/REF3") (class "Default")
      (node (ref "U5") (pin "60") (pinfunction "PD22/PWMH2_60") (pintype "bidirectional"))
    )
    (net (code "156") (name "/REF4") (class "Default")
      (node (ref "U5") (pin "57") (pinfunction "PD23/PWMH3_57") (pintype "bidirectional"))
    )
    (net (code "157") (name "/REF5") (class "Default")
      (node (ref "U5") (pin "55") (pinfunction "PD24/PWML0_55") (pintype "bidirectional"))
    )
    (net (code "159") (name "/REF_EXP1") (class "Default")
      (node (ref "EXP1") (pin "8") (pinfunction "8_8") (pintype "passive"))
      (node (ref "U5") (pin "53") (pinfunction "PD26/PWML2_53") (pintype "bidirectional"))
    )
    (net (code "160") (name "/REF_EXP2") (class "Default")
      (node (ref "EXP1") (pin "13") (pinfunction "13_13") (pintype "passive"))
      (node (ref "U5") (pin "47") (pinfunction "PD27/PWML3_47") (pintype "bidirectional"))
    )
    (net (code "161") (name "/RESET") (class "Default")
      (node (ref "C63") (pin "2") (pinfunction "2_2") (pintype "passive"))
      (node (ref "JTAG/DEBUG1") (pin "10") (pinfunction "10_10") (pintype "passive"))
      (node (ref "R21") (pin "1") (pinfunction "1_1") (pintype "passive"))
      (node (ref "RESET1") (pin "1") (pintype "passive"))
      (node (ref "U5") (pin "83") (pinfunction "NRST_83") (pintype "bidirectional"))
    )
    (net (code "162") (name "/RXD1") (class "Default")
      (node (ref "EXP0") (pin "15") (pinfunction "15_15") (pintype "passive"))
      (node (ref "U5") (pin "32") (pinfunction "PA21/PGMD13/RXD1/PCK1/AFE1_AD2_32") (pintype "bidirectional"))
    )
    (net (code "163") (name "/SAMD21_SS") (class "Default")
      (node (ref "U5") (pin "66") (pinfunction "PA10/PGMD2/UTXD0/NPCS2_66") (pintype "bidirectional"))
    )
    (net (code "164") (name "/SCLK") (class "Default")
      (node (ref "EXP0") (pin "3") (pinfunction "3_3") (pintype "passive"))
      (node (ref "U5") (pin "51") (pinfunction "PA14/PGMD6/SPCK/PWMH3/WKUP8_51") (pintype "bidirectional"))
    )
    (net (code "167") (name "/STEP1") (class "Default")
      (node (ref "U5") (pin "75") (pinfunction "PA9/PGMD1/URXD0/NPCS1/PWMFI0/WKUP6_75") (pintype "bidirectional"))
    )
    (net (code "168") (name "/STEP2") (class "Default")
      (node (ref "U5") (pin "90") (pinfunction "PC10/NANDWE/TCLK7_90") (pintype "bidirectional"))
    )
    (net (code "169") (name "/STEP3") (class "Default")
      (node (ref "U5") (pin "100") (pinfunction "PC16/A21/NANDALE_100") (pintype "bidirectional"))
    )
    (net (code "170") (name "/STEP4") (class "Default")
      (node (ref "U5") (pin "111") (pinfunction "PC18/A0/PWMH0_111") (pintype "bidirectional"))
    )
    (net (code "171") (name "/STEP5") (class "Default")
      (node (ref "U5") (pin "119") (pinfunction "PD7/GRXER_119") (pintype "bidirectional"))
    )
    (net (code "173") (name "/STEP_EXP1") (class "Default")
      (node (ref "EXP1") (pin "4") (pinfunction "4_4") (pintype "passive"))
    )
    (net (code "174") (name "/STEP_EXP2") (class "Default")
      (node (ref "EXP1") (pin "17") (pinfunction "17_17") (pintype "passive"))
    )
    (net (code "175") (name "/TCK{slash}SWDCLK") (class "Default")
      (node (ref "JTAG/DEBUG1") (pin "4") (pinfunction "4_4") (pintype "passive"))
      (node (ref "R25") (pin "1") (pinfunction "1_1") (pintype "passive"))
      (node (ref "U5") (pin "89") (pinfunction "PB7/TCK/SWCLK_89") (pintype "bidirectional"))
    )
    (net (code "180") (name "/TDI") (class "Default")
      (node (ref "JTAG/DEBUG1") (pin "8") (pinfunction "8_8") (pintype "passive"))
      (node (ref "R27") (pin "1") (pinfunction "1_1") (pintype "passive"))
      (node (ref "U5") (pin "105") (pinfunction "PB4/TWD1/PWMH2/TDI_105") (pintype "bidirectional"))
    )
    (net (code "181") (name "/TDO{slash}SWO") (class "Default")
      (node (ref "JTAG/DEBUG1") (pin "6") (pinfunction "6_6") (pintype "passive"))
      (node (ref "R26") (pin "1") (pinfunction "1_1") (pintype "passive"))
      (node (ref "U5") (pin "109") (pinfunction "PB5/TWCK1/PWML0/WKUP13/TDO/TRACESWO_109") (pintype "bidirectional"))
    )
    (net (code "186") (name "/TMS{slash}SWDIO") (class "Default")
      (node (ref "JTAG/DEBUG1") (pin "2") (pinfunction "2_2") (pintype "passive"))
      (node (ref "R24") (pin "1") (pinfunction "1_1") (pintype "passive"))
      (node (ref "U5") (pin "79") (pinfunction "PB6/TMS/SWDIO_79") (pintype "bidirectional"))
    )
    (net (code "187") (name "/TRST") (class "Default")
      (node (ref "R23") (pin "1") (pinfunction "1_1") (pintype "passive"))
      (node (ref "U5") (pin "85") (pinfunction "TEST_85") (pintype "input"))
    )
    (net (code "188") (name "/TXD1") (class "Default")
      (node (ref "EXP0") (pin "6") (pinfunction "6_6") (pintype "passive"))
      (node (ref "U5") (pin "37") (pinfunction "PA22/PGMD14/TXD1/NPCS3/NCS2/AFE1_AD3_37") (pintype "bidirectional"))
    )
    (net (code "189") (name "/UDM_N") (class "Default")
      (node (ref "R19") (pin "1") (pinfunction "1_1") (pintype "passive"))
      (node (ref "U5") (pin "137") (pinfunction "PB11/DDP_137") (pintype "bidirectional"))
    )
    (net (code "190") (name "/UDP_P") (class "Default")
      (node (ref "R17") (pin "1") (pinfunction "1_1") (pintype "passive"))
      (node (ref "U5") (pin "136") (pinfunction "PB10/DDM_136") (pintype "bidirectional"))
    )
    (net (code "191") (name "/USB_VBUS") (class "Default")
      (node (ref "C56") (pin "2") (pinfunction "2_2") (pintype "passive"))
      (node (ref "U6") (pin "14") (pinfunction "VDD2_14") (pintype "passive"))
    )
    (net (code "192") (name "/VDDIN") (class "Default")
      (node (ref "C54") (pin "2") (pinfunction "2_2") (pintype "passive"))
      (node (ref "C55") (pin "2") (pinfunction "2_2") (pintype "passive"))
      (node (ref "FB5") (pin "2") (pinfunction "2_2") (pintype "passive"))
      (node (ref "U5") (pin "5") (pinfunction "VDDIN_5") (pintype "power_in"))
    )
    (net (code "193") (name "/VDDOUT") (class "Default")
      (node (ref "C36") (pin "2") (pinfunction "2_2") (pintype "passive"))
      (node (ref "C37") (pin "2") (pinfunction "2_2") (pintype "passive"))
      (node (ref "C38") (pin "2") (pinfunction "2_2") (pintype "passive"))
      (node (ref "C39") (pin "2") (pinfunction "2_2") (pintype "passive"))
      (node (ref "C40") (pin "2") (pinfunction "2_2") (pintype "passive"))
      (node (ref "C41") (pin "2") (pinfunction "2_2") (pintype "passive"))
      (node (ref "C42") (pin "2") (pinfunction "2_2") (pintype "passive"))
      (node (ref "FB4") (pin "1") (pinfunction "1_1") (pintype "passive"))
      (node (ref "U5") (pin "107") (pinfunction "VDDCORE_107") (pintype "power_in"))
      (node (ref "U5") (pin "123") (pinfunction "VDDCORE_123") (pintype "power_in"))
      (node (ref "U5") (pin "29") (pinfunction "VDDCORE_29") (pintype "power_in"))
      (node (ref "U5") (pin "3") (pinfunction "VDDOUT_3") (pintype "power_in"))
      (node (ref "U5") (pin "33") (pinfunction "VDDCORE_33") (pintype "power_in"))
      (node (ref "U5") (pin "50") (pinfunction "VDDCORE_50") (pintype "power_in"))
      (node (ref "U5") (pin "81") (pinfunction "VDDCORE_81") (pintype "power_in"))
    )
    (net (code "194") (name "/VDDPLL") (class "Default")
      (node (ref "C32") (pin "2") (pinfunction "2_2") (pintype "passive"))
      (node (ref "C33") (pin "2") (pinfunction "2_2") (pintype "passive"))
      (node (ref "FB4") (pin "2") (pinfunction "2_2") (pintype "passive"))
      (node (ref "U5") (pin "139") (pinfunction "VDDPLL_139") (pintype "power_in"))
    )
    (net (code "195") (name "/kRESET") (class "Default")
      (node (ref "EXP0") (pin "4") (pinfunction "4_4") (pintype "passive"))
    )
    (net (code "196") (name "3.3VCC") (class "Default")
      (node (ref "1") (pin "1") (pinfunction "1_1") (pintype "passive"))
      (node (ref "C45") (pin "2") (pinfunction "2_2") (pintype "passive"))
      (node (ref "C46") (pin "2") (pinfunction "2_2") (pintype "passive"))
      (node (ref "C47") (pin "2") (pinfunction "2_2") (pintype "passive"))
      (node (ref "C48") (pin "2") (pinfunction "2_2") (pintype "passive"))
      (node (ref "C49") (pin "2") (pinfunction "2_2") (pintype "passive"))
      (node (ref "C50") (pin "2") (pinfunction "2_2") (pintype "passive"))
      (node (ref "C51") (pin "2") (pinfunction "2_2") (pintype "passive"))
      (node (ref "C60") (pin "2") (pinfunction "2_2") (pintype "passive"))
      (node (ref "C61") (pin "2") (pinfunction "2_2") (pintype "passive"))
      (node (ref "C62") (pin "2") (pinfunction "2_2") (pintype "passive"))
      (node (ref "C64") (pin "2") (pinfunction "2_2") (pintype "passive"))
      (node (ref "EXP0") (pin "12") (pinfunction "12_12") (pintype "passive"))
      (node (ref "EXP0") (pin "9") (pinfunction "9_9") (pintype "passive"))
      (node (ref "EXP1") (pin "12") (pinfunction "12_12") (pintype "passive"))
      (node (ref "EXP1") (pin "9") (pinfunction "9_9") (pintype "passive"))
      (node (ref "FB5") (pin "1") (pinfunction "1_1") (pintype "passive"))
      (node (ref "FB9") (pin "1") (pinfunction "1_1") (pintype "passive"))
      (node (ref "JTAG/DEBUG1") (pin "1") (pinfunction "1_1") (pintype "passive"))
      (node (ref "R21") (pin "2") (pinfunction "2_2") (pintype "passive"))
      (node (ref "R24") (pin "2") (pinfunction "2_2") (pintype "passive"))
      (node (ref "R25") (pin "2") (pinfunction "2_2") (pintype "passive"))
      (node (ref "R26") (pin "2") (pinfunction "2_2") (pintype "passive"))
      (node (ref "R27") (pin "2") (pinfunction "2_2") (pintype "passive"))
      (node (ref "TRST1") (pin "1") (pinfunction "1_1") (pintype "passive"))
      (node (ref "U5") (pin "134") (pinfunction "VDDIO_134") (pintype "power_in"))
      (node (ref "U5") (pin "143") (pinfunction "VDDIO_143") (pintype "power_in"))
      (node (ref "U5") (pin "30") (pinfunction "VDDIO_30") (pintype "power_in"))
      (node (ref "U5") (pin "43") (pinfunction "VDDIO_43") (pintype "power_in"))
      (node (ref "U5") (pin "72") (pinfunction "VDDIO_72") (pintype "power_in"))
      (node (ref "U5") (pin "80") (pinfunction "VDDIO_80") (pintype "power_in"))
      (node (ref "U5") (pin "96") (pinfunction "VDDIO_96") (pintype "power_in"))
    )
    (net (code "197") (name "GND") (class "Default")
      (node (ref "C32") (pin "1") (pinfunction "1_1") (pintype "passive"))
      (node (ref "C33") (pin "1") (pinfunction "1_1") (pintype "passive"))
      (node (ref "C36") (pin "1") (pinfunction "1_1") (pintype "passive"))
      (node (ref "C37") (pin "1") (pinfunction "1_1") (pintype "passive"))
      (node (ref "C38") (pin "1") (pinfunction "1_1") (pintype "passive"))
      (node (ref "C39") (pin "1") (pinfunction "1_1") (pintype "passive"))
      (node (ref "C40") (pin "1") (pinfunction "1_1") (pintype "passive"))
      (node (ref "C41") (pin "1") (pinfunction "1_1") (pintype "passive"))
      (node (ref "C42") (pin "1") (pinfunction "1_1") (pintype "passive"))
      (node (ref "C43") (pin "1") (pinfunction "1_1") (pintype "passive"))
      (node (ref "C44") (pin "1") (pinfunction "1_1") (pintype "passive"))
      (node (ref "C45") (pin "1") (pinfunction "1_1") (pintype "passive"))
      (node (ref "C46") (pin "1") (pinfunction "1_1") (pintype "passive"))
      (node (ref "C47") (pin "1") (pinfunction "1_1") (pintype "passive"))
      (node (ref "C48") (pin "1") (pinfunction "1_1") (pintype "passive"))
      (node (ref "C49") (pin "1") (pinfunction "1_1") (pintype "passive"))
      (node (ref "C50") (pin "1") (pinfunction "1_1") (pintype "passive"))
      (node (ref "C51") (pin "1") (pinfunction "1_1") (pintype "passive"))
      (node (ref "C54") (pin "1") (pinfunction "1_1") (pintype "passive"))
      (node (ref "C55") (pin "1") (pinfunction "1_1") (pintype "passive"))
      (node (ref "C56") (pin "1") (pinfunction "1_1") (pintype "passive"))
      (node (ref "C57") (pin "1") (pinfunction "1_1") (pintype "passive"))
      (node (ref "C60") (pin "1") (pinfunction "1_1") (pintype "passive"))
      (node (ref "C61") (pin "1") (pinfunction "1_1") (pintype "passive"))
      (node (ref "C62") (pin "1") (pinfunction "1_1") (pintype "passive"))
      (node (ref "C63") (pin "1") (pinfunction "1_1") (pintype "passive"))
      (node (ref "C64") (pin "1") (pinfunction "1_1") (pintype "passive"))
      (node (ref "C65") (pin "1") (pinfunction "1_1") (pintype "passive"))
      (node (ref "EXP0") (pin "10") (pinfunction "10_10") (pintype "passive"))
      (node (ref "EXP0") (pin "11") (pinfunction "11_11") (pintype "passive"))
      (node (ref "EXP1") (pin "10") (pinfunction "10_10") (pintype "passive"))
      (node (ref "EXP1") (pin "11") (pinfunction "11_11") (pintype "passive"))
      (node (ref "JTAG/DEBUG1") (pin "3") (pinfunction "3_3") (pintype "passive"))
      (node (ref "JTAG/DEBUG1") (pin "5") (pinfunction "5_5") (pintype "passive"))
      (node (ref "JTAG/DEBUG1") (pin "9") (pinfunction "9_9") (pintype "passive"))
      (node (ref "R15") (pin "2") (pinfunction "2_2") (pintype "passive"))
      (node (ref "R28") (pin "1") (pinfunction "1_1") (pintype "passive"))
      (node (ref "R29") (pin "2") (pinfunction "2_2") (pintype "passive"))
      (node (ref "RESET1") (pin "2") (pintype "passive"))
      (node (ref "SPD1") (pin "3") (pinfunction "3_3") (pintype "passive"))
      (node (ref "U5") (pin "104") (pinfunction "JTAGSEL_104") (pintype "input"))
      (node (ref "U5") (pin "115") (pinfunction "GND_115") (pintype "power_in"))
      (node (ref "U5") (pin "135") (pinfunction "GND_135") (pintype "power_in"))
      (node (ref "U5") (pin "138") (pinfunction "GND_138") (pintype "power_in"))
      (node (ref "U5") (pin "44") (pinfunction "GND_44") (pintype "power_in"))
      (node (ref "U5") (pin "61") (pinfunction "GND_61") (pintype "power_in"))
      (node (ref "U5") (pin "8") (pinfunction "GND_8") (pintype "power_in"))
      (node (ref "U5") (pin "95") (pinfunction "GND_95") (pintype "power_in"))
      (node (ref "U6") (pin "15") (pinfunction "GND2_15") (pintype "passive"))
      (node (ref "U6") (pin "9") (pinfunction "GND2_9") (pintype "passive"))
    )
    (net (code "198") (name "INPUT_GND") (class "Default")
      (node (ref "C58") (pin "1") (pinfunction "1_1") (pintype "passive"))
      (node (ref "C59") (pin "1") (pinfunction "1_1") (pintype "passive"))
      (node (ref "U6") (pin "2") (pinfunction "GND1_2") (pintype "passive"))
      (node (ref "U6") (pin "8") (pinfunction "GND1_8") (pintype "passive"))
      (node (ref "USB") (pin "4") (pinfunction "GND_4") (pintype "passive"))
      (node (ref "USB") (pin "5") (pinfunction "SHLD_5") (pintype "passive"))
      (node (ref "USB") (pin "6") (pinfunction "SHLD_6") (pintype "passive"))
    )
    (net (code "199") (name "Net-(1-Pad2)") (class "Default")
      (node (ref "1") (pin "2") (pinfunction "2_2") (pintype "passive"))
      (node (ref "R22") (pin "2") (pinfunction "2_2") (pintype "passive"))
      (node (ref "R29") (pin "1") (pinfunction "1_1") (pintype "passive"))
    )
    (net (code "200") (name "Net-(R23-Pad2)") (class "Default")
      (node (ref "R23") (pin "2") (pinfunction "2_2") (pintype "passive"))
      (node (ref "R28") (pin "2") (pinfunction "2_2") (pintype "passive"))
      (node (ref "TRST1") (pin "2") (pinfunction "2_2") (pintype "passive"))
    )
    (net (code "201") (name "Net-(U5A-PA29{slash}RI1{slash}TCLK2{slash}MCCK{slash}PIODC5)") (class "Default")
      (node (ref "R15") (pin "1") (pinfunction "1_1") (pintype "passive"))
      (node (ref "R16") (pin "1") (pinfunction "1_1") (pintype "passive"))
      (node (ref "U5") (pin "129") (pinfunction "PA29/RI1/TCLK2/MCCK/PIODC5_129") (pintype "bidirectional"))
    )
    (net (code "202") (name "Net-(U5A-PB8{slash}XOUT)") (class "Default")
      (node (ref "C43") (pin "2") (pinfunction "2_2") (pintype "passive"))
      (node (ref "U5") (pin "141") (pinfunction "PB8/XOUT_141") (pintype "bidirectional"))
      (node (ref "X2") (pin "1") (pinfunction "OSC1_1") (pintype "passive"))
    )
    (net (code "203") (name "Net-(U5A-PB9{slash}XIN)") (class "Default")
      (node (ref "C44") (pin "2") (pinfunction "2_2") (pintype "passive"))
      (node (ref "U5") (pin "142") (pinfunction "PB9/XIN_142") (pintype "bidirectional"))
      (node (ref "X2") (pin "2") (pinfunction "OSC2_2") (pintype "passive"))
    )
    (net (code "204") (name "Net-(U5A-PB14{slash}NPCS1{slash}PWMH3{slash}DAC1)") (class "Default")
      (node (ref "U5") (pin "140") (pinfunction "PB14/NPCS1/PWMH3/DAC1_140") (pintype "bidirectional"))
      (node (ref "U6") (pin "12") (pinfunction "PIN_12") (pintype "passive"))
    )
    (net (code "205") (name "Net-(U6-PDEN)") (class "Default")
      (node (ref "C58") (pin "2") (pinfunction "2_2") (pintype "passive"))
      (node (ref "C59") (pin "2") (pinfunction "2_2") (pintype "passive"))
      (node (ref "U6") (pin "1") (pinfunction "VBUS1_1") (pintype "passive"))
      (node (ref "U6") (pin "3") (pinfunction "VDD1_3") (pintype "passive"))
      (node (ref "U6") (pin "4") (pinfunction "PDEN_4") (pintype "passive"))
      (node (ref "U6") (pin "5") (pinfunction "SPU_5") (pintype "passive"))
      (node (ref "USB") (pin "1") (pinfunction "VBUS_1") (pintype "passive"))
    )
    (net (code "206") (name "Net-(U6-SPD)") (class "Default")
      (node (ref "SPD1") (pin "2") (pinfunction "2_2") (pintype "passive"))
      (node (ref "U6") (pin "13") (pinfunction "SPD_13") (pintype "passive"))
    )
    (net (code "207") (name "Net-(U6-UD+_2)") (class "Default")
      (node (ref "R17") (pin "2") (pinfunction "2_2") (pintype "passive"))
      (node (ref "U6") (pin "10") (pinfunction "UD+_2_10") (pintype "passive"))
    )
    (net (code "208") (name "Net-(U6-UD-_2)") (class "Default")
      (node (ref "R19") (pin "2") (pinfunction "2_2") (pintype "passive"))
      (node (ref "U6") (pin "11") (pinfunction "UD-_2_11") (pintype "passive"))
    )
    (net (code "209") (name "Net-(U6-VBUS2)") (class "Default")
      (node (ref "C57") (pin "2") (pinfunction "2_2") (pintype "passive"))
      (node (ref "R16") (pin "2") (pinfunction "2_2") (pintype "passive"))
      (node (ref "SPD1") (pin "1") (pinfunction "1_1") (pintype "passive"))
      (node (ref "U6") (pin "16") (pinfunction "VBUS2_16") (pintype "passive"))
    )
    (net (code "210") (name "Net-(USB-DM)") (class "Default")
      (node (ref "R18") (pin "2") (pinfunction "2_2") (pintype "passive"))
      (node (ref "USB") (pin "2") (pinfunction "DM_2") (pintype "passive"))
    )
    (net (code "211") (name "Net-(USB-DP)") (class "Default")
      (node (ref "R20") (pin "2") (pinfunction "2_2") (pintype "passive"))
      (node (ref "USB") (pin "3") (pinfunction "DP_3") (pintype "passive"))
    )
    (net (code "212") (name "unconnected-(JTAG/DEBUG1-Pad7)") (class "Default")
      (node (ref "JTAG/DEBUG1") (pin "7") (pinfunction "7_7") (pintype "passive+no_connect"))
    )
    (net (code "213") (name "unconnected-(R22-Pad1)") (class "Default")
      (node (ref "R22") (pin "1") (pinfunction "1_1") (pintype "passive"))
    )
    (net (code "214") (name "unconnected-(U5A-PA7{slash}PGMN3{slash}PWMH3{slash}XIN32-Pad35)") (class "Default")
      (node (ref "U5") (pin "35") (pinfunction "PA7/PGMN3/PWMH3/XIN32_35") (pintype "bidirectional"))
    )
    (net (code "215") (name "unconnected-(U5A-PA23{slash}PGMD15{slash}SCK1{slash}PWMH0{slash}A19{slash}PIODCCLK-Pad46)") (class "Default")
      (node (ref "U5") (pin "46") (pinfunction "PA23/PGMD15/SCK1/PWMH0/A19/PIODCCLK_46") (pintype "bidirectional"))
    )
    (net (code "216") (name "unconnected-(U5A-PA24{slash}RTS1{slash}PWMH1{slash}A20{slash}PIODC0-Pad56)") (class "Default")
      (node (ref "U5") (pin "56") (pinfunction "PA24/RTS1/PWMH1/A20/PIODC0_56") (pintype "bidirectional"))
    )
    (net (code "217") (name "unconnected-(U5A-PA25{slash}CTS1{slash}PWMH2{slash}A23{slash}PIODC1-Pad59)") (class "Default")
      (node (ref "U5") (pin "59") (pinfunction "PA25/CTS1/PWMH2/A23/PIODC1_59") (pintype "bidirectional"))
    )
    (net (code "218") (name "unconnected-(U5A-PA26{slash}DCD1{slash}TIOA2{slash}MCDA2{slash}PIODC2-Pad62)") (class "Default")
      (node (ref "U5") (pin "62") (pinfunction "PA26/DCD1/TIOA2/MCDA2/PIODC2_62") (pintype "bidirectional"))
    )
    (net (code "219") (name "unconnected-(U5A-PA27{slash}DTR1{slash}TIOB2{slash}MCDA3{slash}PIODC3-Pad70)") (class "Default")
      (node (ref "U5") (pin "70") (pinfunction "PA27/DTR1/TIOB2/MCDA3/PIODC3_70") (pintype "bidirectional"))
    )
    (net (code "220") (name "unconnected-(U5A-PB0{slash}PWMH0{slash}RXD0{slash}AFE0_AD4{slash}RTCOUT0-Pad21)") (class "Default")
      (node (ref "U5") (pin "21") (pinfunction "PB0/PWMH0/RXD0/AFE0_AD4/RTCOUT0_21") (pintype "bidirectional"))
    )
    (net (code "221") (name "unconnected-(U5A-PB1{slash}PWMH1{slash}TXD0{slash}AFE0_AD5{slash}RTCOUT1-Pad20)") (class "Default")
      (node (ref "U5") (pin "20") (pinfunction "PB1/PWMH1/TXD0/AFE0_AD5/RTCOUT1_20") (pintype "bidirectional"))
    )
    (net (code "222") (name "unconnected-(U5A-PB3{slash}CANRX0{slash}PCK2{slash}RTS0{slash}AFE1_AD1-Pad31)") (class "Default")
      (node (ref "U5") (pin "31") (pinfunction "PB3/CANRX0/PCK2/RTS0/AFE1_AD1_31") (pintype "bidirectional"))
    )
    (net (code "223") (name "unconnected-(U5A-PB13{slash}PWML2{slash}PCK0{slash}SCK0{slash}DAC0-Pad144)") (class "Default")
      (node (ref "U5") (pin "144") (pinfunction "PB13/PWML2/PCK0/SCK0/DAC0_144") (pintype "bidirectional+no_connect"))
    )
    (net (code "224") (name "unconnected-(U5A-PC0{slash}D0{slash}PWML0{slash}AFE0_AD14-Pad11)") (class "Default")
      (node (ref "U5") (pin "11") (pinfunction "PC0/D0/PWML0/AFE0_AD14_11") (pintype "bidirectional+no_connect"))
    )
    (net (code "225") (name "unconnected-(U5A-PC3{slash}D3{slash}PWML3{slash}AFE1_AD6-Pad40)") (class "Default")
      (node (ref "U5") (pin "40") (pinfunction "PC3/D3/PWML3/AFE1_AD6_40") (pintype "bidirectional"))
    )
    (net (code "226") (name "unconnected-(U5A-PC4{slash}D4{slash}NPCS1{slash}AFE1_AD7-Pad41)") (class "Default")
      (node (ref "U5") (pin "41") (pinfunction "PC4/D4/NPCS1/AFE1_AD7_41") (pintype "bidirectional"))
    )
    (net (code "227") (name "unconnected-(U5A-PC5{slash}D5{slash}TIOA6-Pad58)") (class "Default")
      (node (ref "U5") (pin "58") (pinfunction "PC5/D5/TIOA6_58") (pintype "bidirectional"))
    )
    (net (code "228") (name "unconnected-(U5A-PC6{slash}D6{slash}TIOB6-Pad54)") (class "Default")
      (node (ref "U5") (pin "54") (pinfunction "PC6/D6/TIOB6_54") (pintype "bidirectional"))
    )
    (net (code "229") (name "unconnected-(U5A-PC7{slash}D7{slash}TCLK6-Pad48)") (class "Default")
      (node (ref "U5") (pin "48") (pinfunction "PC7/D7/TCLK6_48") (pintype "bidirectional"))
    )
    (net (code "230") (name "unconnected-(U5A-PC12{slash}NCS3{slash}TIOB8{slash}CANRX1{slash}AFE0_AD8-Pad17)") (class "Default")
      (node (ref "U5") (pin "17") (pinfunction "PC12/NCS3/TIOB8/CANRX1/AFE0_AD8_17") (pintype "bidirectional"))
    )
    (net (code "231") (name "unconnected-(U5A-PC13{slash}NWAIT{slash}PWML0{slash}AFE0_AD6-Pad19)") (class "Default")
      (node (ref "U5") (pin "19") (pinfunction "PC13/NWAIT/PWML0/AFE0_AD6_19") (pintype "bidirectional"))
    )
    (net (code "232") (name "unconnected-(U5A-PC15{slash}NCS1{slash}PWML1{slash}CANTX1{slash}AFE0_AD7-Pad18)") (class "Default")
      (node (ref "U5") (pin "18") (pinfunction "PC15/NCS1/PWML1/CANTX1/AFE0_AD7_18") (pintype "bidirectional+no_connect"))
    )
    (net (code "233") (name "unconnected-(U5A-PC22{slash}A4{slash}PWML3-Pad124)") (class "Default")
      (node (ref "U5") (pin "124") (pinfunction "PC22/A4/PWML3_124") (pintype "bidirectional"))
    )
    (net (code "234") (name "unconnected-(U5A-PC23{slash}A5{slash}TIOA3-Pad127)") (class "Default")
      (node (ref "U5") (pin "127") (pinfunction "PC23/A5/TIOA3_127") (pintype "bidirectional"))
    )
    (net (code "235") (name "unconnected-(U5A-PC24{slash}A6{slash}TIOB3-Pad130)") (class "Default")
      (node (ref "U5") (pin "130") (pinfunction "PC24/A6/TIOB3_130") (pintype "bidirectional+no_connect"))
    )
    (net (code "236") (name "unconnected-(U5A-PC25{slash}A7{slash}TCLK3-Pad133)") (class "Default")
      (node (ref "U5") (pin "133") (pinfunction "PC25/A7/TCLK3_133") (pintype "bidirectional+no_connect"))
    )
    (net (code "237") (name "unconnected-(U5A-PC26{slash}A8{slash}TIOA4{slash}AFE0_AD12-Pad13)") (class "Default")
      (node (ref "U5") (pin "13") (pinfunction "PC26/A8/TIOA4/AFE0_AD12_13") (pintype "bidirectional"))
    )
    (net (code "238") (name "unconnected-(U5A-PC27{slash}A9{slash}TIOB4{slash}AFE0_AD13-Pad12)") (class "Default")
      (node (ref "U5") (pin "12") (pinfunction "PC27/A9/TIOB4/AFE0_AD13_12") (pintype "bidirectional"))
    )
    (net (code "239") (name "unconnected-(U5A-PC29{slash}A11{slash}TIOA5{slash}AFE0_AD9-Pad16)") (class "Default")
      (node (ref "U5") (pin "16") (pinfunction "PC29/A11/TIOA5/AFE0_AD9_16") (pintype "bidirectional"))
    )
    (net (code "240") (name "unconnected-(U5A-PC30{slash}A12{slash}TIOB5{slash}AFE0_AD10-Pad15)") (class "Default")
      (node (ref "U5") (pin "15") (pinfunction "PC30/A12/TIOB5/AFE0_AD10_15") (pintype "bidirectional"))
    )
    (net (code "241") (name "unconnected-(U5A-PC31{slash}A13{slash}TCLK5{slash}AFE0_AD11-Pad14)") (class "Default")
      (node (ref "U5") (pin "14") (pinfunction "PC31/A13/TCLK5/AFE0_AD11_14") (pintype "bidirectional"))
    )
    (net (code "242") (name "unconnected-(U5A-PD0{slash}GTXCK{slash}GREFCK-Pad1)") (class "Default")
      (node (ref "U5") (pin "1") (pinfunction "PD0/GTXCK/GREFCK_1") (pintype "bidirectional+no_connect"))
    )
    (net (code "243") (name "unconnected-(U5A-PD1{slash}GTXEN-Pad132)") (class "Default")
      (node (ref "U5") (pin "132") (pinfunction "PD1/GTXEN_132") (pintype "bidirectional"))
    )
    (net (code "244") (name "unconnected-(U5A-PD2{slash}GTX0-Pad131)") (class "Default")
      (node (ref "U5") (pin "131") (pinfunction "PD2/GTX0_131") (pintype "bidirectional"))
    )
    (net (code "245") (name "unconnected-(U5A-PD3{slash}GTX1-Pad128)") (class "Default")
      (node (ref "U5") (pin "128") (pinfunction "PD3/GTX1_128") (pintype "bidirectional"))
    )
    (net (code "246") (name "unconnected-(U5A-PD4{slash}GCRSDV{slash}GRXDV-Pad126)") (class "Default")
      (node (ref "U5") (pin "126") (pinfunction "PD4/GCRSDV/GRXDV_126") (pintype "bidirectional"))
    )
    (net (code "247") (name "unconnected-(U5A-PD5{slash}GRX0-Pad125)") (class "Default")
      (node (ref "U5") (pin "125") (pinfunction "PD5/GRX0_125") (pintype "bidirectional"))
    )
    (net (code "248") (name "unconnected-(U5A-PD18{slash}NCS1-Pad69)") (class "Default")
      (node (ref "U5") (pin "69") (pinfunction "PD18/NCS1_69") (pintype "bidirectional"))
    )
    (net (code "249") (name "unconnected-(U5A-PD19{slash}NCS3-Pad67)") (class "Default")
      (node (ref "U5") (pin "67") (pinfunction "PD19/NCS3_67") (pintype "bidirectional"))
    )
    (net (code "250") (name "unconnected-(U5A-PD25{slash}PWML1-Pad52)") (class "Default")
      (node (ref "U5") (pin "52") (pinfunction "PD25/PWML1_52") (pintype "bidirectional"))
    )
    (net (code "251") (name "unconnected-(U5A-PD30-Pad34)") (class "Default")
      (node (ref "U5") (pin "34") (pinfunction "PD30_34") (pintype "bidirectional"))
    )
    (net (code "252") (name "unconnected-(U5A-PD31-Pad2)") (class "Default")
      (node (ref "U5") (pin "2") (pinfunction "PD31_2") (pintype "bidirectional"))
    )
    (net (code "253") (name "unconnected-(U5A-PE0-Pad4)") (class "Default")
      (node (ref "U5") (pin "4") (pinfunction "PE0_4") (pintype "bidirectional"))
    )
    (net (code "254") (name "unconnected-(U5A-PE1-Pad6)") (class "Default")
      (node (ref "U5") (pin "6") (pinfunction "PE1_6") (pintype "bidirectional"))
    )
    (net (code "255") (name "unconnected-(U5A-PE2-Pad7)") (class "Default")
      (node (ref "U5") (pin "7") (pinfunction "PE2_7") (pintype "bidirectional"))
    )
    (net (code "256") (name "unconnected-(U5A-PE3-Pad10)") (class "Default")
      (node (ref "U5") (pin "10") (pinfunction "PE3_10") (pintype "bidirectional"))
    )
    (net (code "257") (name "unconnected-(U5A-PE5-Pad28)") (class "Default")
      (node (ref "U5") (pin "28") (pinfunction "PE5_28") (pintype "bidirectional"))
    )
  )
)
